# Mother_Board_Driver_Interface.net
KiCad netlist of a schematic drawn in Altium Designer
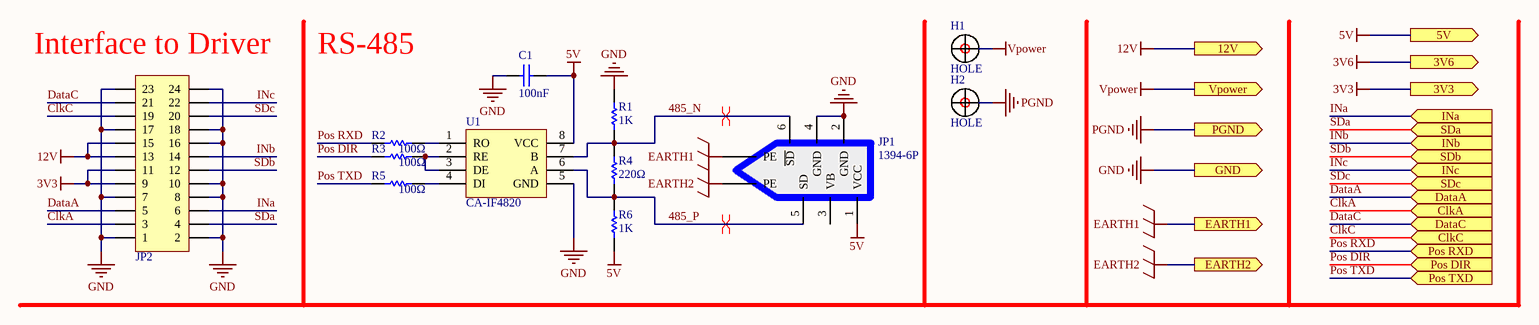
[diagram p0: Mother Board Driver Interface.SchDoc]

(export (version "E")
  (design (tool "Eeschema 10.0.6"))
  (components
    (comp (ref "C1") (value "100nF") (footprint "C0603") (libsource (lib "Cap") (part "Cap")))
    (comp (ref "H1") (value "HOLE") (footprint "定位孔 Φ3 1") (libsource (lib "mylib") (part "HOLE")))
    (comp (ref "H2") (value "HOLE") (footprint "定位孔 Φ3 1") (libsource (lib "mylib") (part "HOLE")))
    (comp (ref "JP1")
      (value "1394-6P")
      (footprint "1394-6P")
      (description "IEEE 1394 FireWire接口")
      (libsource (lib "All lib") (part "1394-6P"))
    )
    (comp (ref "JP2")
      (value "Header 2X12")
      (footprint "HEADER_0.8mm_2x12P_M")
      (description "12*2P接插件")
      (fields (field (name "版权归属") "源创客"))
      (libsource (lib "All lib") (part "Header 12PX2"))
    )
    (comp (ref "R1") (value "1K") (footprint "R0603") (libsource (lib "Res") (part "RES")))
    (comp (ref "R2") (value "100Ω") (footprint "R0603") (libsource (lib "Res") (part "RES")))
    (comp (ref "R3") (value "100Ω") (footprint "R0603") (libsource (lib "Res") (part "RES")))
    (comp (ref "R4") (value "220Ω") (footprint "R0603") (libsource (lib "Res") (part "RES")))
    (comp (ref "R5") (value "100Ω") (footprint "R0603") (libsource (lib "Res") (part "RES")))
    (comp (ref "R6") (value "1K") (footprint "R0603") (libsource (lib "Res") (part "RES")))
    (comp (ref "U1")
      (value "CA-IF4820")
      (footprint "SOP8_N")
      (description "485总线芯片")
      (libsource (lib "All lib") (part "CA-IF4820"))
    )
  )
  (nets
    (net (code "1") (name "/485_N") (class "Default")
      (node (ref "JP1") (pin "6") (pinfunction "~{SD}_6") (pintype "passive"))
      (node (ref "R1") (pin "1") (pinfunction "1_1") (pintype "passive"))
      (node (ref "R4") (pin "2") (pinfunction "2_2") (pintype "passive"))
      (node (ref "U1") (pin "7") (pinfunction "B_7") (pintype "passive"))
    )
    (net (code "2") (name "/485_P") (class "Default")
      (node (ref "JP1") (pin "5") (pinfunction "SD_5") (pintype "passive"))
      (node (ref "R4") (pin "1") (pinfunction "1_1") (pintype "passive"))
      (node (ref "R6") (pin "2") (pinfunction "2_2") (pintype "passive"))
      (node (ref "U1") (pin "6") (pinfunction "A_6") (pintype "passive"))
    )
    (net (code "3") (name "/ClkA") (class "Default")
      (node (ref "JP2") (pin "3") (pinfunction "3_3") (pintype "passive"))
    )
    (net (code "4") (name "/ClkC") (class "Default")
      (node (ref "JP2") (pin "19") (pinfunction "19_19") (pintype "passive"))
    )
    (net (code "5") (name "/DataA") (class "Default")
      (node (ref "JP2") (pin "5") (pinfunction "5_5") (pintype "passive"))
    )
    (net (code "6") (name "/DataC") (class "Default")
      (node (ref "JP2") (pin "21") (pinfunction "21_21") (pintype "passive"))
    )
    (net (code "7") (name "/INa") (class "Default")
      (node (ref "JP2") (pin "6") (pinfunction "6_6") (pintype "passive"))
    )
    (net (code "8") (name "/INb") (class "Default")
      (node (ref "JP2") (pin "14") (pinfunction "14_14") (pintype "passive"))
    )
    (net (code "9") (name "/INc") (class "Default")
      (node (ref "JP2") (pin "22") (pinfunction "22_22") (pintype "passive"))
    )
    (net (code "10") (name "/Pos DIR") (class "Default")
      (node (ref "R3") (pin "1") (pinfunction "1_1") (pintype "passive"))
    )
    (net (code "11") (name "/Pos RXD") (class "Default")
      (node (ref "R2") (pin "1") (pinfunction "1_1") (pintype "passive"))
    )
    (net (code "12") (name "/Pos TXD") (class "Default")
      (node (ref "R5") (pin "1") (pinfunction "1_1") (pintype "passive"))
    )
    (net (code "13") (name "/SDa") (class "Default")
      (node (ref "JP2") (pin "4") (pinfunction "4_4") (pintype "passive"))
    )
    (net (code "14") (name "/SDb") (class "Default")
      (node (ref "JP2") (pin "12") (pinfunction "12_12") (pintype "passive"))
    )
    (net (code "15") (name "/SDc") (class "Default")
      (node (ref "JP2") (pin "20") (pinfunction "20_20") (pintype "passive"))
    )
    (net (code "16") (name "3V3") (class "Default")
      (node (ref "JP2") (pin "11") (pinfunction "11_11") (pintype "passive"))
      (node (ref "JP2") (pin "9") (pinfunction "9_9") (pintype "passive"))
    )
    (net (code "18") (name "5V") (class "Default")
      (node (ref "C1") (pin "2") (pinfunction "2_2") (pintype "passive"))
      (node (ref "JP1") (pin "1") (pinfunction "VCC_1") (pintype "passive"))
      (node (ref "R6") (pin "1") (pinfunction "1_1") (pintype "passive"))
      (node (ref "U1") (pin "8") (pinfunction "VCC_8") (pintype "passive"))
    )
    (net (code "19") (name "12V") (class "Default")
      (node (ref "JP2") (pin "13") (pinfunction "13_13") (pintype "passive"))
      (node (ref "JP2") (pin "15") (pinfunction "15_15") (pintype "passive"))
    )
    (net (code "20") (name "EARTH1") (class "Default")
      (node (ref "JP1") (pin "7") (pinfunction "PE_7") (pintype "passive"))
    )
    (net (code "21") (name "EARTH2") (class "Default")
      (node (ref "JP1") (pin "8") (pinfunction "PE_8") (pintype "passive"))
    )
    (net (code "22") (name "GND") (class "Default")
      (node (ref "C1") (pin "1") (pinfunction "1_1") (pintype "passive"))
      (node (ref "JP1") (pin "2") (pinfunction "GND_2") (pintype "passive"))
      (node (ref "JP1") (pin "4") (pinfunction "GND_4") (pintype "passive"))
      (node (ref "JP2") (pin "1") (pinfunction "1_1") (pintype "passive"))
      (node (ref "JP2") (pin "10") (pinfunction "10_10") (pintype "passive"))
      (node (ref "JP2") (pin "16") (pinfunction "16_16") (pintype "passive"))
      (node (ref "JP2") (pin "17") (pinfunction "17_17") (pintype "passive"))
      (node (ref "JP2") (pin "18") (pinfunction "18_18") (pintype "passive"))
      (node (ref "JP2") (pin "2") (pinfunction "2_2") (pintype "passive"))
      (node (ref "JP2") (pin "23") (pinfunction "23_23") (pintype "passive"))
      (node (ref "JP2") (pin "24") (pinfunction "24_24") (pintype "passive"))
      (node (ref "JP2") (pin "7") (pinfunction "7_7") (pintype "passive"))
      (node (ref "JP2") (pin "8") (pinfunction "8_8") (pintype "passive"))
      (node (ref "R1") (pin "2") (pinfunction "2_2") (pintype "passive"))
      (node (ref "U1") (pin "5") (pinfunction "GND_5") (pintype "passive"))
    )
    (net (code "23") (name "Net-(U1-DE)") (class "Default")
      (node (ref "R3") (pin "2") (pinfunction "2_2") (pintype "passive"))
      (node (ref "U1") (pin "2") (pinfunction "RE_2") (pintype "passive"))
      (node (ref "U1") (pin "3") (pinfunction "DE_3") (pintype "passive"))
    )
    (net (code "24") (name "Net-(U1-DI)") (class "Default")
      (node (ref "R5") (pin "2") (pinfunction "2_2") (pintype "passive"))
      (node (ref "U1") (pin "4") (pinfunction "DI_4") (pintype "passive"))
    )
    (net (code "25") (name "Net-(U1-RO)") (class "Default")
      (node (ref "R2") (pin "2") (pinfunction "2_2") (pintype "passive"))
      (node (ref "U1") (pin "1") (pinfunction "RO_1") (pintype "passive"))
    )
    (net (code "26") (name "PGND") (class "Default") (node (ref "H2") (pin "1") (pintype "passive")))
    (net (code "27") (name "Vpower") (class "Default") (node (ref "H1") (pin "1") (pintype "passive")))
    (net (code "28") (name "unconnected-(JP1-VB-Pad3)") (class "Default")
      (node (ref "JP1") (pin "3") (pinfunction "VB_3") (pintype "passive"))
    )
  )
)
